# cpu.net
KiCad netlist of a schematic drawn in EAGLE
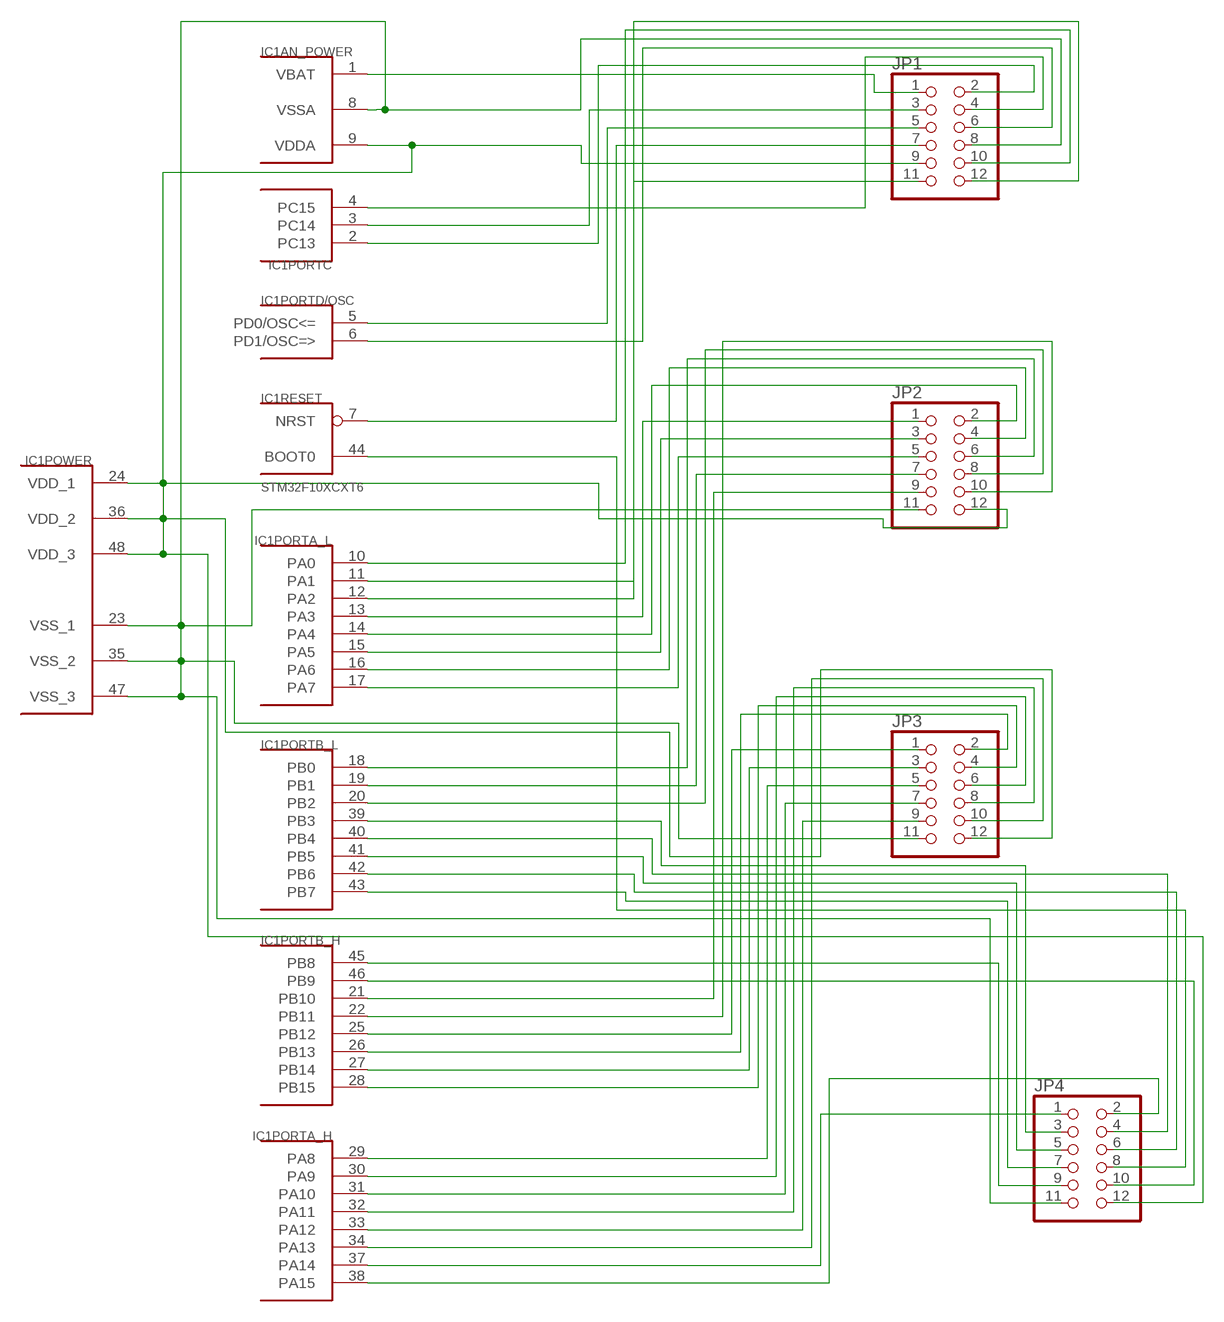
[diagram p0: schematic, sheet 1]

(export (version "E")
  (design (tool "Eeschema 10.0.6"))
  (components
    (comp (ref "IC1")
      (value "STM32F10XCXT6")
      (footprint "eagle-import:TQFP48")
      (libsource (lib "eagle-import") (part "STM32F10XCXT6"))
    )
    (comp (ref "JP1")
      (value "PINHD-2X6")
      (footprint "eagle-import:2X06")
      (libsource (lib "eagle-import") (part "PINHD-2X6"))
    )
    (comp (ref "JP2")
      (value "PINHD-2X6")
      (footprint "eagle-import:2X06")
      (libsource (lib "eagle-import") (part "PINHD-2X6"))
    )
    (comp (ref "JP3")
      (value "PINHD-2X6")
      (footprint "eagle-import:2X06")
      (libsource (lib "eagle-import") (part "PINHD-2X6"))
    )
    (comp (ref "JP4")
      (value "PINHD-2X6")
      (footprint "eagle-import:2X06")
      (libsource (lib "eagle-import") (part "PINHD-2X6"))
    )
  )
  (nets
    (net (code "1") (name "Net-(IC1A-VBAT)") (class "Default")
      (node (ref "IC1") (pin "1") (pinfunction "VBAT_1") (pintype "power_in"))
      (node (ref "JP1") (pin "1") (pinfunction "1_1") (pintype "passive"))
    )
    (net (code "2") (name "Net-(IC1A-VDDA)") (class "Default")
      (node (ref "IC1") (pin "24") (pinfunction "VDD_1_24") (pintype "power_in"))
      (node (ref "IC1") (pin "36") (pinfunction "VDD_2_36") (pintype "power_in"))
      (node (ref "IC1") (pin "48") (pinfunction "VDD_3_48") (pintype "power_in"))
      (node (ref "IC1") (pin "9") (pinfunction "VDDA_9") (pintype "power_in"))
      (node (ref "JP1") (pin "9") (pinfunction "9_9") (pintype "passive"))
      (node (ref "JP2") (pin "12") (pinfunction "12_12") (pintype "passive"))
      (node (ref "JP3") (pin "12") (pinfunction "12_12") (pintype "passive"))
      (node (ref "JP4") (pin "12") (pinfunction "12_12") (pintype "passive"))
    )
    (net (code "3") (name "Net-(IC1A-VSSA)") (class "Default")
      (node (ref "IC1") (pin "23") (pinfunction "VSS_1_23") (pintype "power_in"))
      (node (ref "IC1") (pin "35") (pinfunction "VSS_2_35") (pintype "power_in"))
      (node (ref "IC1") (pin "47") (pinfunction "VSS_3_47") (pintype "power_in"))
      (node (ref "IC1") (pin "8") (pinfunction "VSSA_8") (pintype "power_in"))
      (node (ref "JP1") (pin "8") (pinfunction "8_8") (pintype "passive"))
      (node (ref "JP2") (pin "11") (pinfunction "11_11") (pintype "passive"))
      (node (ref "JP3") (pin "11") (pinfunction "11_11") (pintype "passive"))
      (node (ref "JP4") (pin "11") (pinfunction "11_11") (pintype "passive"))
    )
    (net (code "4") (name "Net-(IC1B-PA8)") (class "Default")
      (node (ref "IC1") (pin "29") (pinfunction "PA8_29") (pintype "bidirectional"))
      (node (ref "JP3") (pin "5") (pinfunction "5_5") (pintype "passive"))
    )
    (net (code "5") (name "Net-(IC1B-PA9)") (class "Default")
      (node (ref "IC1") (pin "30") (pinfunction "PA9_30") (pintype "bidirectional"))
      (node (ref "JP3") (pin "6") (pinfunction "6_6") (pintype "passive"))
    )
    (net (code "6") (name "Net-(IC1B-PA10)") (class "Default")
      (node (ref "IC1") (pin "31") (pinfunction "PA10_31") (pintype "bidirectional"))
      (node (ref "JP3") (pin "7") (pinfunction "7_7") (pintype "passive"))
    )
    (net (code "7") (name "Net-(IC1B-PA11)") (class "Default")
      (node (ref "IC1") (pin "32") (pinfunction "PA11_32") (pintype "bidirectional"))
      (node (ref "JP3") (pin "8") (pinfunction "8_8") (pintype "passive"))
    )
    (net (code "8") (name "Net-(IC1B-PA12)") (class "Default")
      (node (ref "IC1") (pin "33") (pinfunction "PA12_33") (pintype "bidirectional"))
      (node (ref "JP3") (pin "9") (pinfunction "9_9") (pintype "passive"))
    )
    (net (code "9") (name "Net-(IC1B-PA13)") (class "Default")
      (node (ref "IC1") (pin "34") (pinfunction "PA13_34") (pintype "bidirectional"))
      (node (ref "JP3") (pin "10") (pinfunction "10_10") (pintype "passive"))
    )
    (net (code "10") (name "Net-(IC1B-PA14)") (class "Default")
      (node (ref "IC1") (pin "37") (pinfunction "PA14_37") (pintype "bidirectional"))
      (node (ref "JP4") (pin "1") (pinfunction "1_1") (pintype "passive"))
    )
    (net (code "11") (name "Net-(IC1B-PA15)") (class "Default")
      (node (ref "IC1") (pin "38") (pinfunction "PA15_38") (pintype "bidirectional"))
      (node (ref "JP4") (pin "2") (pinfunction "2_2") (pintype "passive"))
    )
    (net (code "12") (name "Net-(IC1C-PA0)") (class "Default")
      (node (ref "IC1") (pin "10") (pinfunction "PA0_10") (pintype "bidirectional"))
      (node (ref "JP1") (pin "10") (pinfunction "10_10") (pintype "passive"))
    )
    (net (code "13") (name "Net-(IC1C-PA1)") (class "Default")
      (node (ref "IC1") (pin "11") (pinfunction "PA1_11") (pintype "bidirectional"))
      (node (ref "JP1") (pin "11") (pinfunction "11_11") (pintype "passive"))
    )
    (net (code "14") (name "Net-(IC1C-PA2)") (class "Default")
      (node (ref "IC1") (pin "12") (pinfunction "PA2_12") (pintype "bidirectional"))
      (node (ref "JP1") (pin "12") (pinfunction "12_12") (pintype "passive"))
    )
    (net (code "15") (name "Net-(IC1C-PA3)") (class "Default")
      (node (ref "IC1") (pin "13") (pinfunction "PA3_13") (pintype "bidirectional"))
      (node (ref "JP2") (pin "1") (pinfunction "1_1") (pintype "passive"))
    )
    (net (code "16") (name "Net-(IC1C-PA4)") (class "Default")
      (node (ref "IC1") (pin "14") (pinfunction "PA4_14") (pintype "bidirectional"))
      (node (ref "JP2") (pin "2") (pinfunction "2_2") (pintype "passive"))
    )
    (net (code "17") (name "Net-(IC1C-PA5)") (class "Default")
      (node (ref "IC1") (pin "15") (pinfunction "PA5_15") (pintype "bidirectional"))
      (node (ref "JP2") (pin "3") (pinfunction "3_3") (pintype "passive"))
    )
    (net (code "18") (name "Net-(IC1C-PA6)") (class "Default")
      (node (ref "IC1") (pin "16") (pinfunction "PA6_16") (pintype "bidirectional"))
      (node (ref "JP2") (pin "4") (pinfunction "4_4") (pintype "passive"))
    )
    (net (code "19") (name "Net-(IC1C-PA7)") (class "Default")
      (node (ref "IC1") (pin "17") (pinfunction "PA7_17") (pintype "bidirectional"))
      (node (ref "JP2") (pin "5") (pinfunction "5_5") (pintype "passive"))
    )
    (net (code "20") (name "Net-(IC1D-PB8)") (class "Default")
      (node (ref "IC1") (pin "45") (pinfunction "PB8_45") (pintype "bidirectional"))
      (node (ref "JP4") (pin "9") (pinfunction "9_9") (pintype "passive"))
    )
    (net (code "21") (name "Net-(IC1D-PB9)") (class "Default")
      (node (ref "IC1") (pin "46") (pinfunction "PB9_46") (pintype "bidirectional"))
      (node (ref "JP4") (pin "10") (pinfunction "10_10") (pintype "passive"))
    )
    (net (code "22") (name "Net-(IC1D-PB10)") (class "Default")
      (node (ref "IC1") (pin "21") (pinfunction "PB10_21") (pintype "bidirectional"))
      (node (ref "JP2") (pin "9") (pinfunction "9_9") (pintype "passive"))
    )
    (net (code "23") (name "Net-(IC1D-PB11)") (class "Default")
      (node (ref "IC1") (pin "22") (pinfunction "PB11_22") (pintype "bidirectional"))
      (node (ref "JP2") (pin "10") (pinfunction "10_10") (pintype "passive"))
    )
    (net (code "24") (name "Net-(IC1D-PB12)") (class "Default")
      (node (ref "IC1") (pin "25") (pinfunction "PB12_25") (pintype "bidirectional"))
      (node (ref "JP3") (pin "1") (pinfunction "1_1") (pintype "passive"))
    )
    (net (code "25") (name "Net-(IC1D-PB13)") (class "Default")
      (node (ref "IC1") (pin "26") (pinfunction "PB13_26") (pintype "bidirectional"))
      (node (ref "JP3") (pin "2") (pinfunction "2_2") (pintype "passive"))
    )
    (net (code "26") (name "Net-(IC1D-PB14)") (class "Default")
      (node (ref "IC1") (pin "27") (pinfunction "PB14_27") (pintype "bidirectional"))
      (node (ref "JP3") (pin "3") (pinfunction "3_3") (pintype "passive"))
    )
    (net (code "27") (name "Net-(IC1D-PB15)") (class "Default")
      (node (ref "IC1") (pin "28") (pinfunction "PB15_28") (pintype "bidirectional"))
      (node (ref "JP3") (pin "4") (pinfunction "4_4") (pintype "passive"))
    )
    (net (code "28") (name "Net-(IC1E-PB0)") (class "Default")
      (node (ref "IC1") (pin "18") (pinfunction "PB0_18") (pintype "bidirectional"))
      (node (ref "JP2") (pin "6") (pinfunction "6_6") (pintype "passive"))
    )
    (net (code "29") (name "Net-(IC1E-PB1)") (class "Default")
      (node (ref "IC1") (pin "19") (pinfunction "PB1_19") (pintype "bidirectional"))
      (node (ref "JP2") (pin "7") (pinfunction "7_7") (pintype "passive"))
    )
    (net (code "30") (name "Net-(IC1E-PB2)") (class "Default")
      (node (ref "IC1") (pin "20") (pinfunction "PB2_20") (pintype "bidirectional"))
      (node (ref "JP2") (pin "8") (pinfunction "8_8") (pintype "passive"))
    )
    (net (code "31") (name "Net-(IC1E-PB3)") (class "Default")
      (node (ref "IC1") (pin "39") (pinfunction "PB3_39") (pintype "bidirectional"))
      (node (ref "JP4") (pin "3") (pinfunction "3_3") (pintype "passive"))
    )
    (net (code "32") (name "Net-(IC1E-PB4)") (class "Default")
      (node (ref "IC1") (pin "40") (pinfunction "PB4_40") (pintype "bidirectional"))
      (node (ref "JP4") (pin "4") (pinfunction "4_4") (pintype "passive"))
    )
    (net (code "33") (name "Net-(IC1E-PB5)") (class "Default")
      (node (ref "IC1") (pin "41") (pinfunction "PB5_41") (pintype "bidirectional"))
      (node (ref "JP4") (pin "5") (pinfunction "5_5") (pintype "passive"))
    )
    (net (code "34") (name "Net-(IC1E-PB6)") (class "Default")
      (node (ref "IC1") (pin "42") (pinfunction "PB6_42") (pintype "bidirectional"))
      (node (ref "JP4") (pin "6") (pinfunction "6_6") (pintype "passive"))
    )
    (net (code "35") (name "Net-(IC1E-PB7)") (class "Default")
      (node (ref "IC1") (pin "43") (pinfunction "PB7_43") (pintype "bidirectional"))
      (node (ref "JP4") (pin "7") (pinfunction "7_7") (pintype "passive"))
    )
    (net (code "36") (name "Net-(IC1F-PC13)") (class "Default")
      (node (ref "IC1") (pin "2") (pinfunction "PC13_2") (pintype "bidirectional"))
      (node (ref "JP1") (pin "2") (pinfunction "2_2") (pintype "passive"))
    )
    (net (code "37") (name "Net-(IC1F-PC14)") (class "Default")
      (node (ref "IC1") (pin "3") (pinfunction "PC14_3") (pintype "bidirectional"))
      (node (ref "JP1") (pin "3") (pinfunction "3_3") (pintype "passive"))
    )
    (net (code "38") (name "Net-(IC1F-PC15)") (class "Default")
      (node (ref "IC1") (pin "4") (pinfunction "PC15_4") (pintype "bidirectional"))
      (node (ref "JP1") (pin "4") (pinfunction "4_4") (pintype "passive"))
    )
    (net (code "39") (name "Net-(IC1G-PD0{slash}OSC<=)") (class "Default")
      (node (ref "IC1") (pin "5") (pinfunction "PD0/OSC<=_5") (pintype "bidirectional"))
      (node (ref "JP1") (pin "5") (pinfunction "5_5") (pintype "passive"))
    )
    (net (code "40") (name "Net-(IC1G-PD1{slash}OSC=>)") (class "Default")
      (node (ref "IC1") (pin "6") (pinfunction "PD1/OSC=>_6") (pintype "bidirectional"))
      (node (ref "JP1") (pin "6") (pinfunction "6_6") (pintype "passive"))
    )
    (net (code "41") (name "Net-(IC1I-BOOT0)") (class "Default")
      (node (ref "IC1") (pin "44") (pinfunction "BOOT0_44") (pintype "input"))
      (node (ref "JP4") (pin "8") (pinfunction "8_8") (pintype "passive"))
    )
    (net (code "42") (name "Net-(IC1I-NRST)") (class "Default")
      (node (ref "IC1") (pin "7") (pinfunction "NRST_7") (pintype "input"))
      (node (ref "JP1") (pin "7") (pinfunction "7_7") (pintype "passive"))
    )
  )
)
